# 8_-GSM_MODEM_CONNECTORS.net
KiCad netlist of a schematic drawn in Altium Designer
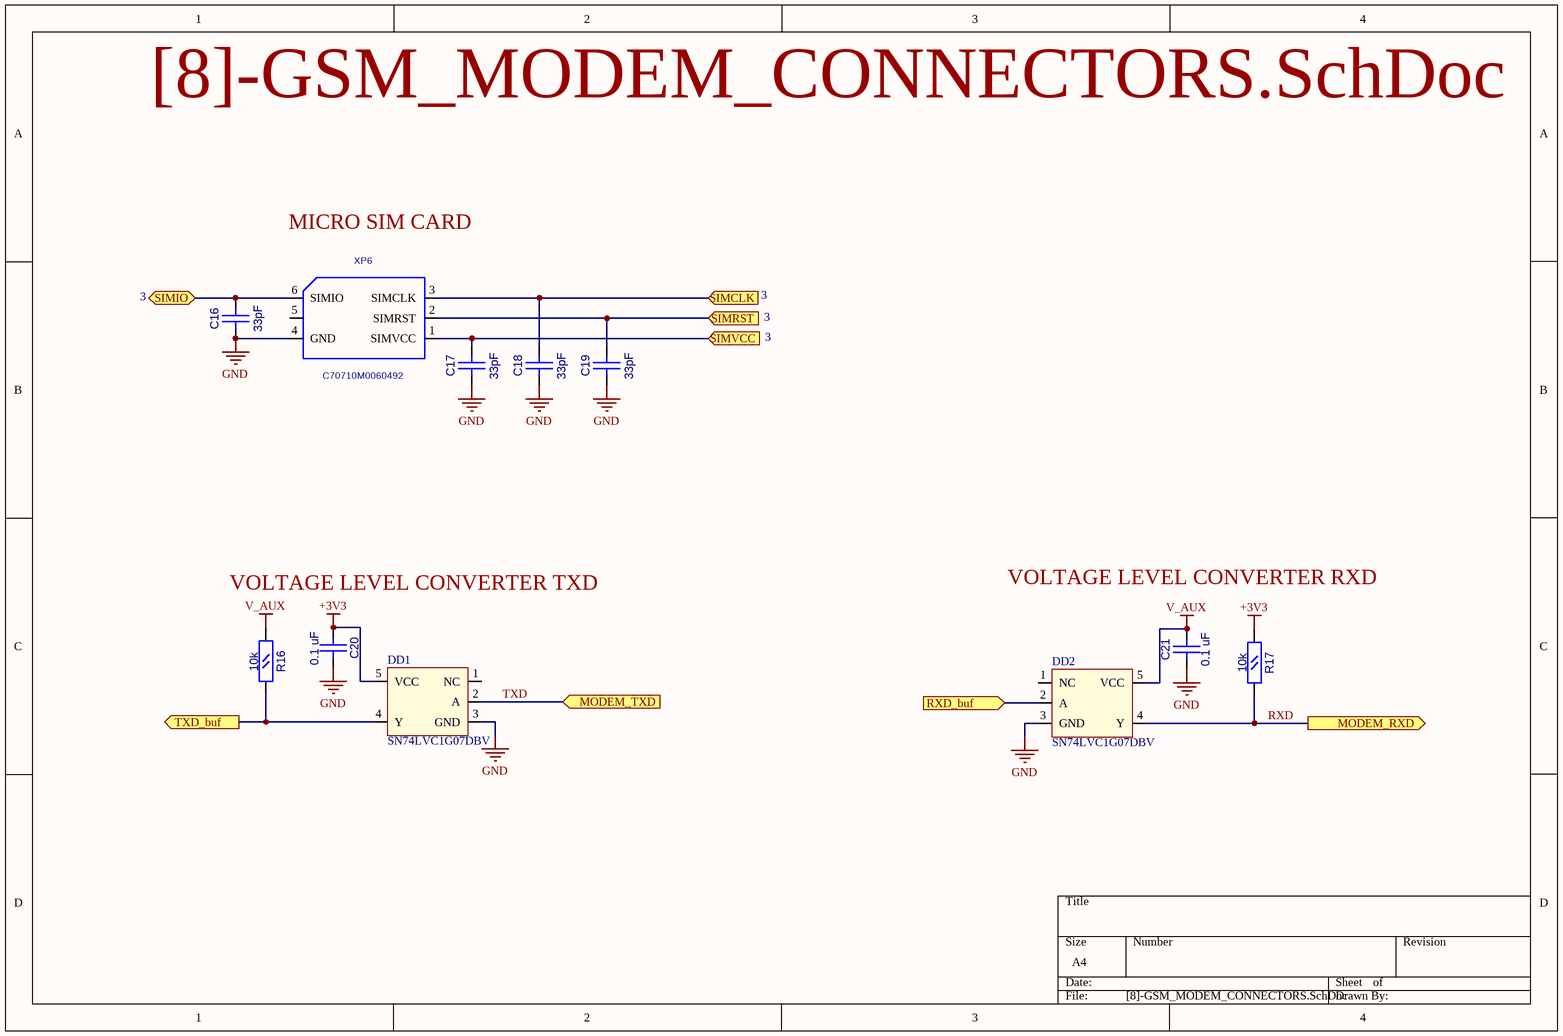
[diagram p0: [8]-GSM_MODEM_CONNECTORS.SchDoc]

(export (version "E")
  (design (tool "Eeschema 10.0.6"))
  (components
    (comp (ref "C16")
      (value "33pF")
      (footprint "CC0603")
      (description "CC0603")
      (libsource (lib "gprs_modem_2") (part "CC0603"))
    )
    (comp (ref "C17")
      (value "33pF")
      (footprint "CC0603")
      (description "CC0603")
      (libsource (lib "gprs_modem_2") (part "CC0603"))
    )
    (comp (ref "C18")
      (value "33pF")
      (footprint "CC0603")
      (description "CC0603")
      (libsource (lib "gprs_modem_2") (part "CC0603"))
    )
    (comp (ref "C19")
      (value "33pF")
      (footprint "CC0603")
      (description "CC0603")
      (libsource (lib "gprs_modem_2") (part "CC0603"))
    )
    (comp (ref "C20")
      (value "0.1 uF")
      (footprint "CC0603")
      (description "CC0603")
      (libsource (lib "gprs_modem_2") (part "CC0603"))
    )
    (comp (ref "C21")
      (value "0.1 uF")
      (footprint "CC0603")
      (description "CC0603")
      (libsource (lib "gprs_modem_2") (part "CC0603"))
    )
    (comp (ref "DD1")
      (value "SN74LVC1G07DBV")
      (footprint "SOT23-5")
      (description "Open Drain Single Bus Bufer")
      (libsource (lib "gprs_modem_2") (part "SN74LVC1G07DBV"))
    )
    (comp (ref "DD2")
      (value "SN74LVC1G07DBV")
      (footprint "SOT23-5")
      (description "Open Drain Single Bus Bufer")
      (libsource (lib "") (part "SN74LVC1G07DBV_1"))
    )
    (comp (ref "R16")
      (value "10k")
      (footprint "RC0603")
      (description "RC0603")
      (libsource (lib "gprs_modem_2") (part "RC0603"))
    )
    (comp (ref "R17")
      (value "10k")
      (footprint "RC0603")
      (description "RC0603")
      (libsource (lib "gprs_modem_2") (part "RC0603"))
    )
    (comp (ref "XP6")
      (value "C70710M0060492")
      (footprint "SCVW06A25020")
      (description "SCV-W06A25-020")
      (libsource (lib "gprs_modem_2") (part "SCV-W06A25-020"))
    )
  )
  (nets
    (net (code "1") (name "+3V3") (class "Default")
      (node (ref "C20") (pin "2") (pinfunction "B_2") (pintype "passive"))
      (node (ref "DD1") (pin "5") (pinfunction "VCC_5") (pintype "passive"))
      (node (ref "R17") (pin "1") (pinfunction "A_1") (pintype "passive"))
    )
    (net (code "2") (name "/RXD") (class "Default")
      (node (ref "DD2") (pin "4") (pinfunction "Y_4") (pintype "passive"))
      (node (ref "R17") (pin "2") (pinfunction "B_2") (pintype "passive"))
    )
    (net (code "3") (name "/RXD_buf") (class "Default")
      (node (ref "DD2") (pin "2") (pinfunction "A_2") (pintype "passive"))
    )
    (net (code "4") (name "/SIMCLK") (class "Default")
      (node (ref "C18") (pin "2") (pinfunction "B_2") (pintype "passive"))
      (node (ref "XP6") (pin "3") (pinfunction "SIMCLK_3") (pintype "passive"))
    )
    (net (code "5") (name "/SIMIO") (class "Default")
      (node (ref "C16") (pin "2") (pinfunction "B_2") (pintype "passive"))
      (node (ref "XP6") (pin "6") (pinfunction "SIMIO_6") (pintype "passive"))
    )
    (net (code "6") (name "/SIMRST") (class "Default")
      (node (ref "C19") (pin "2") (pinfunction "B_2") (pintype "passive"))
      (node (ref "XP6") (pin "2") (pinfunction "SIMRST_2") (pintype "passive"))
    )
    (net (code "7") (name "/SIMVCC") (class "Default")
      (node (ref "C17") (pin "2") (pinfunction "B_2") (pintype "passive"))
      (node (ref "XP6") (pin "1") (pinfunction "SIMVCC_1") (pintype "passive"))
    )
    (net (code "8") (name "/TXD") (class "Default")
      (node (ref "DD1") (pin "2") (pinfunction "A_2") (pintype "passive"))
    )
    (net (code "9") (name "/TXD_buf") (class "Default")
      (node (ref "DD1") (pin "4") (pinfunction "Y_4") (pintype "passive"))
      (node (ref "R16") (pin "2") (pinfunction "B_2") (pintype "passive"))
    )
    (net (code "10") (name "GND") (class "Default")
      (node (ref "C16") (pin "1") (pinfunction "A_1") (pintype "passive"))
      (node (ref "C17") (pin "1") (pinfunction "A_1") (pintype "passive"))
      (node (ref "C18") (pin "1") (pinfunction "A_1") (pintype "passive"))
      (node (ref "C19") (pin "1") (pinfunction "A_1") (pintype "passive"))
      (node (ref "C20") (pin "1") (pinfunction "A_1") (pintype "passive"))
      (node (ref "C21") (pin "1") (pinfunction "A_1") (pintype "passive"))
      (node (ref "DD1") (pin "3") (pinfunction "GND_3") (pintype "passive"))
      (node (ref "DD2") (pin "3") (pinfunction "GND_3") (pintype "passive"))
      (node (ref "XP6") (pin "4") (pinfunction "GND_4") (pintype "passive"))
    )
    (net (code "11") (name "V_AUX") (class "Default")
      (node (ref "C21") (pin "2") (pinfunction "B_2") (pintype "passive"))
      (node (ref "DD2") (pin "5") (pinfunction "VCC_5") (pintype "passive"))
      (node (ref "R16") (pin "1") (pinfunction "A_1") (pintype "passive"))
    )
    (net (code "12") (name "unconnected-(DD1-NC-Pad1)") (class "Default")
      (node (ref "DD1") (pin "1") (pinfunction "NC_1") (pintype "passive"))
    )
    (net (code "13") (name "unconnected-(DD2-NC-Pad1)") (class "Default")
      (node (ref "DD2") (pin "1") (pinfunction "NC_1") (pintype "passive"))
    )
    (net (code "14") (name "unconnected-(XP6-Pad5)") (class "Default")
      (node (ref "XP6") (pin "5") (pintype "passive"))
    )
  )
)
